# SLBMM.net
KiCad netlist of a schematic drawn in Altium Designer
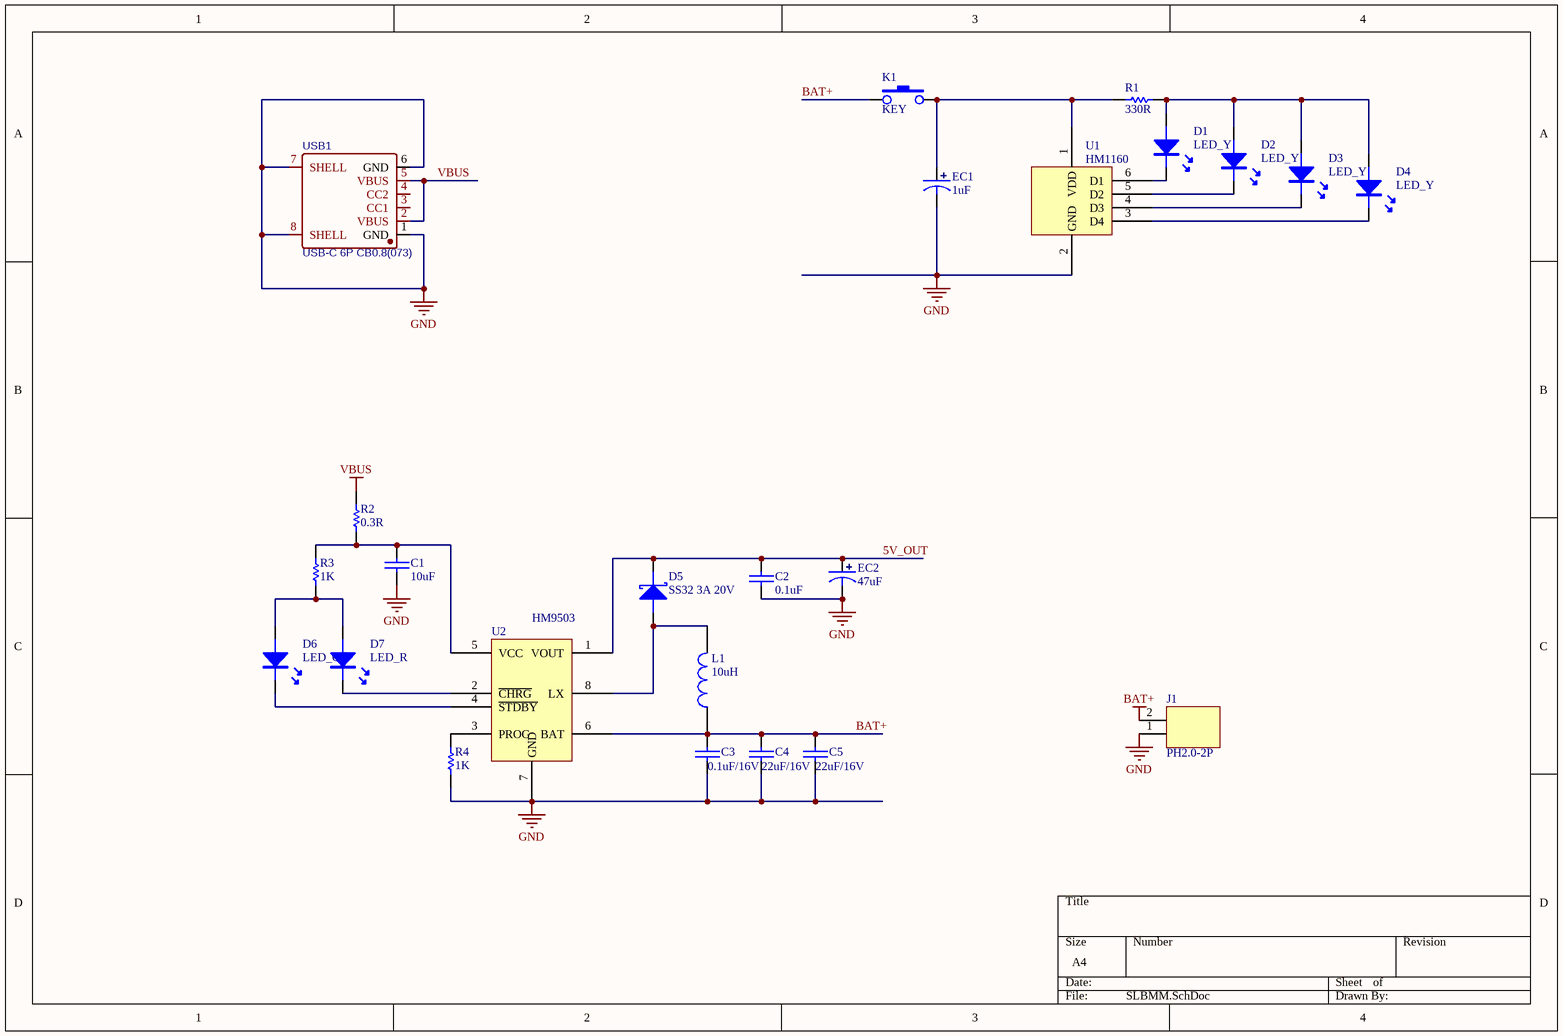
[diagram p0: SLBMM.SchDoc]

(export (version "E")
  (design (tool "Eeschema 10.0.6"))
  (components
    (comp (ref "C1")
      (value "10uF")
      (footprint "0603C")
      (description "无极性电容")
      (libsource (lib "电容") (part "CAP"))
    )
    (comp (ref "C2")
      (value "0.1uF")
      (footprint "0603C")
      (description "无极性电容")
      (libsource (lib "电容") (part "CAP"))
    )
    (comp (ref "C3")
      (value "0.1uF/16V")
      (footprint "0603C")
      (description "无极性电容")
      (libsource (lib "电容") (part "CAP"))
    )
    (comp (ref "C4")
      (value "22uF/16V")
      (footprint "0603C")
      (description "无极性电容")
      (libsource (lib "电容") (part "CAP"))
    )
    (comp (ref "C5")
      (value "22uF/16V")
      (footprint "0603C")
      (description "无极性电容")
      (libsource (lib "电容") (part "CAP"))
    )
    (comp (ref "D1") (value "LED_Y") (footprint "LED-0603Y") (libsource (lib "LED") (part "LED")))
    (comp (ref "D2") (value "LED_Y") (footprint "LED-0603Y") (libsource (lib "LED") (part "LED")))
    (comp (ref "D3") (value "LED_Y") (footprint "LED-0603Y") (libsource (lib "LED") (part "LED")))
    (comp (ref "D4") (value "LED_Y") (footprint "LED-0603Y") (libsource (lib "LED") (part "LED")))
    (comp (ref "D5")
      (value "SS32 3A 20V")
      (footprint "SMA/DO-214AC")
      (description "肖特基二极管")
      (libsource (lib "二极管") (part "DIODE SCHOTTKY"))
    )
    (comp (ref "D6") (value "LED_G") (footprint "LED-0603G") (libsource (lib "LED") (part "LED")))
    (comp (ref "D7") (value "LED_R") (footprint "LED-0603B") (libsource (lib "LED") (part "LED")))
    (comp (ref "EC1")
      (value "1uF")
      (footprint "SMD-EC4.0X4.3X5.4")
      (description "贴片电解电容")
      (libsource (lib "电容") (part "SMD_ECAP"))
    )
    (comp (ref "EC2")
      (value "47uF")
      (footprint "SMD-EC4.0X4.3X5.4")
      (description "贴片电解电容")
      (libsource (lib "电容") (part "SMD_ECAP"))
    )
    (comp (ref "J1") (value "PH2.0-2P") (footprint "PH2.0-2P") (libsource (lib "PH") (part "PH2.0-2P")))
    (comp (ref "K1") (value "KEY") (footprint "SMD-3.5x7.8x2.5_C") (libsource (lib "轻触开关") (part "KEY")))
    (comp (ref "L1")
      (value "10uH")
      (footprint "0630L")
      (description "INDUCTOR")
      (libsource (lib "电感") (part "INDUCTOR"))
    )
    (comp (ref "R1") (value "330R") (footprint "0603R") (libsource (lib "电阻") (part "RES")))
    (comp (ref "R2") (value "0.3R") (footprint "0603R") (libsource (lib "电阻") (part "RES")))
    (comp (ref "R3") (value "1K") (footprint "0603R") (libsource (lib "电阻") (part "RES")))
    (comp (ref "R4") (value "1K") (footprint "0603R") (libsource (lib "电阻") (part "RES")))
    (comp (ref "U1")
      (value "HM1160")
      (footprint "SOT23-6")
      (description "单节锂电池电量指示芯片")
      (libsource (lib "电源芯片") (part "HM1160"))
    )
    (comp (ref "U2")
      (value "HM9503")
      (footprint "ESOP8")
      (description "1A锂电池充电和5V/1A升压控制\r\n芯片")
      (libsource (lib "电源芯片") (part "HM9503"))
    )
    (comp (ref "USB1")
      (value "USB-C 6P CB0.8(073)")
      (footprint "USB-C-SMD_TYPE-C-6P-CB0.8-073")
      (fields
        (field (name "BOM_SUPPLIER PART") "C2858273")
        (field (name "BOM_MANUFACTURER PART") "TYPE-C 6P CB0.8(073)")
        (field (name "CONTRIBUTOR") "LCSC")
      )
      (libsource (lib "USB") (part "USB-C 6P CB0.8(073)"))
    )
  )
  (nets
    (net (code "1") (name "/5V_OUT") (class "Default")
      (node (ref "C2") (pin "2") (pinfunction "2_2") (pintype "passive"))
      (node (ref "D5") (pin "K") (pinfunction "K_K") (pintype "passive"))
      (node (ref "EC2") (pin "1") (pinfunction "1_1") (pintype "passive"))
      (node (ref "U2") (pin "1") (pinfunction "VOUT_1") (pintype "passive"))
    )
    (net (code "2") (name "BAT+") (class "Default")
      (node (ref "C3") (pin "2") (pinfunction "2_2") (pintype "passive"))
      (node (ref "C4") (pin "2") (pinfunction "2_2") (pintype "passive"))
      (node (ref "C5") (pin "2") (pinfunction "2_2") (pintype "passive"))
      (node (ref "J1") (pin "2") (pinfunction "2_2") (pintype "passive"))
      (node (ref "K1") (pin "1") (pinfunction "1_1") (pintype "passive"))
      (node (ref "L1") (pin "1") (pinfunction "1_1") (pintype "passive"))
      (node (ref "U2") (pin "6") (pinfunction "BAT_6") (pintype "passive"))
    )
    (net (code "3") (name "GND") (class "Default")
      (node (ref "C1") (pin "1") (pinfunction "1_1") (pintype "passive"))
      (node (ref "C2") (pin "1") (pinfunction "1_1") (pintype "passive"))
      (node (ref "C3") (pin "1") (pinfunction "1_1") (pintype "passive"))
      (node (ref "C4") (pin "1") (pinfunction "1_1") (pintype "passive"))
      (node (ref "C5") (pin "1") (pinfunction "1_1") (pintype "passive"))
      (node (ref "EC1") (pin "2") (pinfunction "2_2") (pintype "passive"))
      (node (ref "EC2") (pin "2") (pinfunction "2_2") (pintype "passive"))
      (node (ref "J1") (pin "1") (pinfunction "1_1") (pintype "passive"))
      (node (ref "R4") (pin "1") (pinfunction "1_1") (pintype "passive"))
      (node (ref "U1") (pin "2") (pinfunction "GND_2") (pintype "passive"))
      (node (ref "U2") (pin "7") (pinfunction "GND_7") (pintype "passive"))
      (node (ref "USB1") (pin "1") (pinfunction "GND_1") (pintype "passive"))
      (node (ref "USB1") (pin "6") (pinfunction "GND_6") (pintype "passive"))
      (node (ref "USB1") (pin "7") (pinfunction "SHELL_7") (pintype "passive"))
      (node (ref "USB1") (pin "8") (pinfunction "SHELL_8") (pintype "passive"))
    )
    (net (code "4") (name "Net-(D1-PadA)") (class "Default")
      (node (ref "D1") (pin "A") (pinfunction "A_A") (pintype "passive"))
      (node (ref "D2") (pin "A") (pinfunction "A_A") (pintype "passive"))
      (node (ref "D3") (pin "A") (pinfunction "A_A") (pintype "passive"))
      (node (ref "D4") (pin "A") (pinfunction "A_A") (pintype "passive"))
      (node (ref "R1") (pin "1") (pinfunction "1_1") (pintype "passive"))
    )
    (net (code "5") (name "Net-(D6-PadA)") (class "Default")
      (node (ref "D6") (pin "A") (pinfunction "A_A") (pintype "passive"))
      (node (ref "D7") (pin "A") (pinfunction "A_A") (pintype "passive"))
      (node (ref "R3") (pin "1") (pinfunction "1_1") (pintype "passive"))
    )
    (net (code "6") (name "Net-(U1-D1)") (class "Default")
      (node (ref "D1") (pin "K") (pinfunction "K_K") (pintype "passive"))
      (node (ref "U1") (pin "6") (pinfunction "D1_6") (pintype "passive"))
    )
    (net (code "7") (name "Net-(U1-D2)") (class "Default")
      (node (ref "D2") (pin "K") (pinfunction "K_K") (pintype "passive"))
      (node (ref "U1") (pin "5") (pinfunction "D2_5") (pintype "passive"))
    )
    (net (code "8") (name "Net-(U1-D3)") (class "Default")
      (node (ref "D3") (pin "K") (pinfunction "K_K") (pintype "passive"))
      (node (ref "U1") (pin "4") (pinfunction "D3_4") (pintype "passive"))
    )
    (net (code "9") (name "Net-(U1-D4)") (class "Default")
      (node (ref "D4") (pin "K") (pinfunction "K_K") (pintype "passive"))
      (node (ref "U1") (pin "3") (pinfunction "D4_3") (pintype "passive"))
    )
    (net (code "10") (name "Net-(U1-VDD)") (class "Default")
      (node (ref "EC1") (pin "1") (pinfunction "1_1") (pintype "passive"))
      (node (ref "K1") (pin "3") (pinfunction "3_3") (pintype "passive"))
      (node (ref "R1") (pin "2") (pinfunction "2_2") (pintype "passive"))
      (node (ref "U1") (pin "1") (pinfunction "VDD_1") (pintype "passive"))
    )
    (net (code "11") (name "Net-(U2-LX)") (class "Default")
      (node (ref "D5") (pin "A") (pinfunction "A_A") (pintype "passive"))
      (node (ref "L1") (pin "2") (pinfunction "2_2") (pintype "passive"))
      (node (ref "U2") (pin "8") (pinfunction "LX_8") (pintype "passive"))
    )
    (net (code "12") (name "Net-(U2-PROG)") (class "Default")
      (node (ref "R4") (pin "2") (pinfunction "2_2") (pintype "passive"))
      (node (ref "U2") (pin "3") (pinfunction "PROG_3") (pintype "passive"))
    )
    (net (code "13") (name "Net-(U2-VCC)") (class "Default")
      (node (ref "C1") (pin "2") (pinfunction "2_2") (pintype "passive"))
      (node (ref "R2") (pin "1") (pinfunction "1_1") (pintype "passive"))
      (node (ref "R3") (pin "2") (pinfunction "2_2") (pintype "passive"))
      (node (ref "U2") (pin "5") (pinfunction "VCC_5") (pintype "passive"))
    )
    (net (code "14") (name "Net-(U2-~{CHRG})") (class "Default")
      (node (ref "D7") (pin "K") (pinfunction "K_K") (pintype "passive"))
      (node (ref "U2") (pin "2") (pinfunction "~{CHRG}_2") (pintype "passive"))
    )
    (net (code "15") (name "Net-(U2-~{STDBY})") (class "Default")
      (node (ref "D6") (pin "K") (pinfunction "K_K") (pintype "passive"))
      (node (ref "U2") (pin "4") (pinfunction "~{STDBY}_4") (pintype "passive"))
    )
    (net (code "16") (name "VBUS") (class "Default")
      (node (ref "R2") (pin "2") (pinfunction "2_2") (pintype "passive"))
      (node (ref "USB1") (pin "2") (pinfunction "VBUS_2") (pintype "passive"))
      (node (ref "USB1") (pin "5") (pinfunction "VBUS_5") (pintype "passive"))
    )
    (net (code "17") (name "unconnected-(USB1-CC1-Pad3)") (class "Default")
      (node (ref "USB1") (pin "3") (pinfunction "CC1_3") (pintype "passive"))
    )
    (net (code "18") (name "unconnected-(USB1-CC2-Pad4)") (class "Default")
      (node (ref "USB1") (pin "4") (pinfunction "CC2_4") (pintype "passive"))
    )
  )
)
